# atmega128rf.net
KiCad netlist of a schematic drawn in Altium Designer
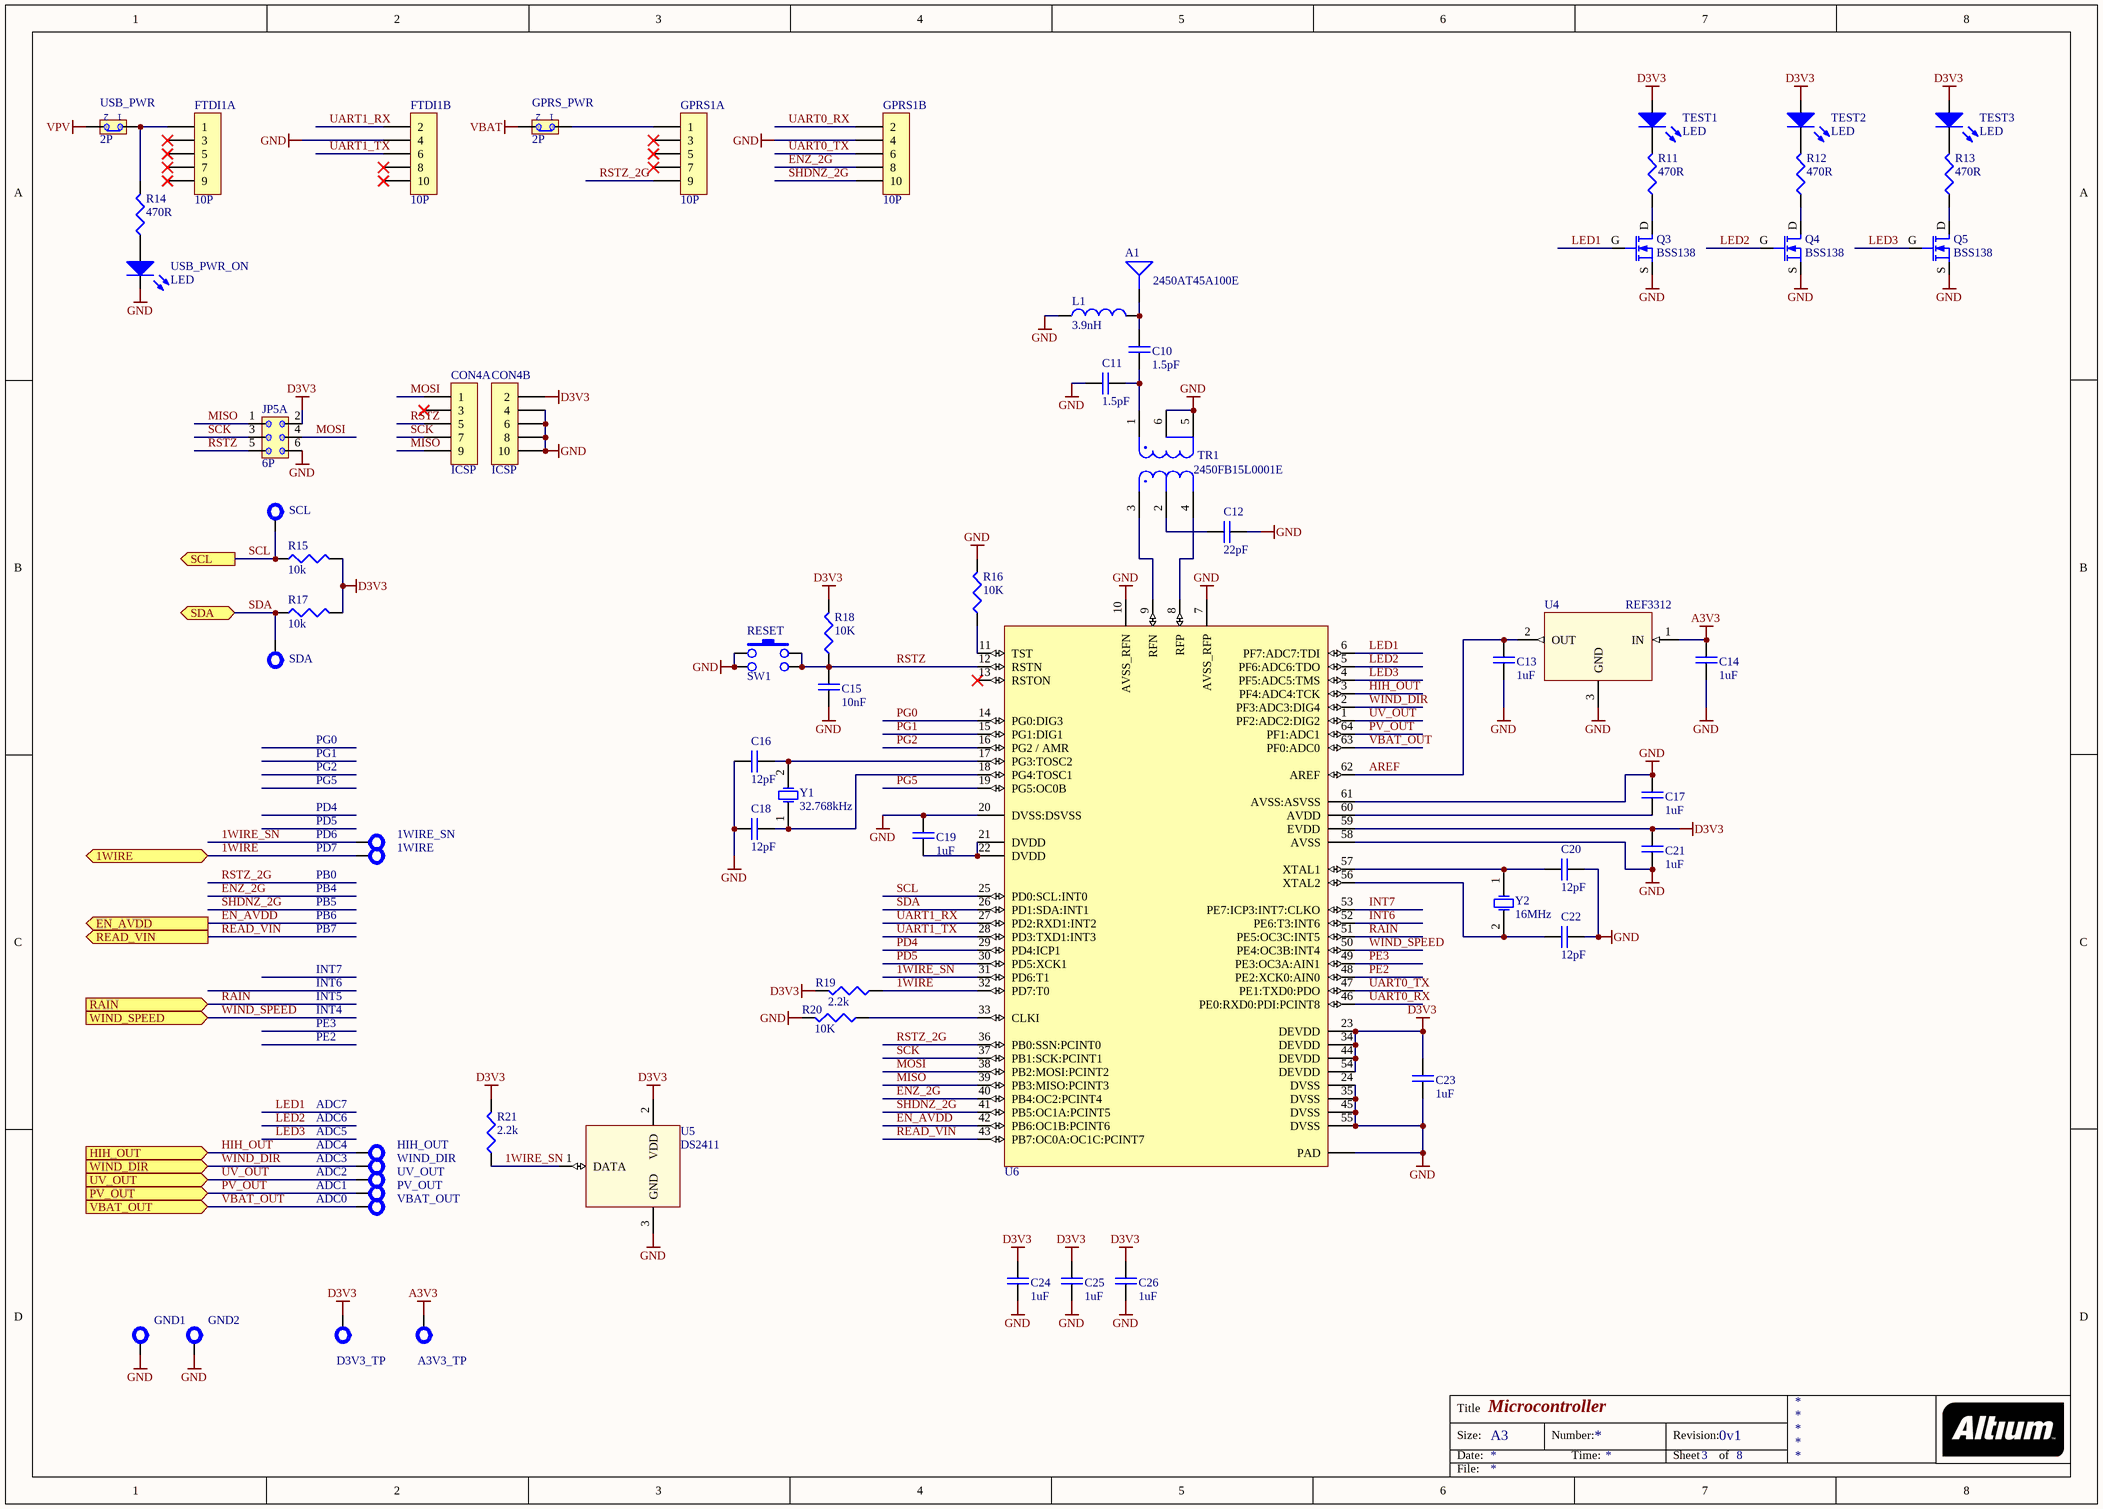
[diagram p0: atmega128rf.SchDoc]

(export (version "E")
  (design (tool "Eeschema 10.0.6"))
  (components
    (comp (ref "1WIRE")
      (value "Test Point")
      (footprint "TERMINAL")
      (description "Test/Probe Point")
      (fields (field (name "OWNER") "Nuno Brum"))
      (libsource (lib "Alcetronics_EM") (part "TEST-PROBE"))
    )
    (comp (ref "1WIRE_SN")
      (value "Test Point")
      (footprint "TERMINAL")
      (description "Test/Probe Point")
      (fields (field (name "OWNER") "Nuno Brum"))
      (libsource (lib "Alcetronics_EM") (part "TEST-PROBE"))
    )
    (comp (ref "A1")
      (value "2450AT45A100E")
      (footprint "2450AT45A100E")
      (description "ANTENNA")
      (libsource (lib "Alcetronics_Devices") (part "Antenna SE"))
    )
    (comp (ref "A3V3_TP")
      (value "Test Point")
      (footprint "TERMINAL")
      (description "Test/Probe Point")
      (fields (field (name "OWNER") "Nuno Brum"))
      (libsource (lib "Alcetronics_EM") (part "TEST-PROBE"))
    )
    (comp (ref "C10")
      (value "1.5pF")
      (footprint "0402")
      (description "Capacitor")
      (fields (field (name "OWNER") "Nuno Brum"))
      (libsource (lib "Alcetronics_Devices") (part "CAP"))
    )
    (comp (ref "C11")
      (value "1.5pF")
      (footprint "0402")
      (description "Capacitor")
      (fields (field (name "OWNER") "Nuno Brum"))
      (libsource (lib "Alcetronics_Devices") (part "CAP"))
    )
    (comp (ref "C12")
      (value "22pF")
      (footprint "0402")
      (description "Capacitor")
      (fields (field (name "OWNER") "Nuno Brum"))
      (libsource (lib "Alcetronics_Devices") (part "CAP"))
    )
    (comp (ref "C13")
      (value "1uF")
      (footprint "0603")
      (description "Capacitor")
      (fields (field (name "OWNER") "Nuno Brum"))
      (libsource (lib "Alcetronics_Devices") (part "CAP"))
    )
    (comp (ref "C14")
      (value "1uF")
      (footprint "0603")
      (description "Capacitor")
      (fields (field (name "OWNER") "Nuno Brum"))
      (libsource (lib "Alcetronics_Devices") (part "CAP"))
    )
    (comp (ref "C15")
      (value "10nF")
      (footprint "0603")
      (description "Capacitor")
      (fields (field (name "OWNER") "Nuno Brum"))
      (libsource (lib "Alcetronics_Devices") (part "CAP"))
    )
    (comp (ref "C16")
      (value "12pF")
      (footprint "0603")
      (description "Capacitor")
      (fields (field (name "OWNER") "Nuno Brum"))
      (libsource (lib "Alcetronics_Devices") (part "CAP"))
    )
    (comp (ref "C17")
      (value "1uF")
      (footprint "0603")
      (description "Capacitor")
      (fields (field (name "OWNER") "Nuno Brum"))
      (libsource (lib "Alcetronics_Devices") (part "CAP"))
    )
    (comp (ref "C18")
      (value "12pF")
      (footprint "0603")
      (description "Capacitor")
      (fields (field (name "OWNER") "Nuno Brum"))
      (libsource (lib "Alcetronics_Devices") (part "CAP"))
    )
    (comp (ref "C19")
      (value "1uF")
      (footprint "0603")
      (description "Capacitor")
      (fields (field (name "OWNER") "Nuno Brum"))
      (libsource (lib "Alcetronics_Devices") (part "CAP"))
    )
    (comp (ref "C20")
      (value "12pF")
      (footprint "0603")
      (description "Capacitor")
      (fields (field (name "OWNER") "Nuno Brum"))
      (libsource (lib "Alcetronics_Devices") (part "CAP"))
    )
    (comp (ref "C21")
      (value "1uF")
      (footprint "0603")
      (description "Capacitor")
      (fields (field (name "OWNER") "Nuno Brum"))
      (libsource (lib "Alcetronics_Devices") (part "CAP"))
    )
    (comp (ref "C22")
      (value "12pF")
      (footprint "0603")
      (description "Capacitor")
      (fields (field (name "OWNER") "Nuno Brum"))
      (libsource (lib "Alcetronics_Devices") (part "CAP"))
    )
    (comp (ref "C23")
      (value "1uF")
      (footprint "0603")
      (description "Capacitor")
      (fields (field (name "OWNER") "Nuno Brum"))
      (libsource (lib "Alcetronics_Devices") (part "CAP"))
    )
    (comp (ref "C24")
      (value "1uF")
      (footprint "0603")
      (description "Capacitor")
      (fields (field (name "OWNER") "Nuno Brum"))
      (libsource (lib "Alcetronics_Devices") (part "CAP"))
    )
    (comp (ref "C25")
      (value "1uF")
      (footprint "0603")
      (description "Capacitor")
      (fields (field (name "OWNER") "Nuno Brum"))
      (libsource (lib "Alcetronics_Devices") (part "CAP"))
    )
    (comp (ref "C26")
      (value "1uF")
      (footprint "0603")
      (description "Capacitor")
      (fields (field (name "OWNER") "Nuno Brum"))
      (libsource (lib "Alcetronics_Devices") (part "CAP"))
    )
    (comp (ref "CON4")
      (value "ICSP")
      (footprint "IDC-10-F")
      (description "Connector 10 Pins")
      (fields (field (name "OWNER") "António Silva"))
      (libsource (lib "Alcetronics_EM") (part "CON10"))
    )
    (comp (ref "D3V3_TP")
      (value "Test Point")
      (footprint "TERMINAL")
      (description "Test/Probe Point")
      (fields (field (name "OWNER") "Nuno Brum"))
      (libsource (lib "Alcetronics_EM") (part "TEST-PROBE"))
    )
    (comp (ref "FTDI1")
      (value "10P")
      (footprint "IDC-10-90")
      (description "Connector 10 Pins")
      (fields (field (name "OWNER") "António Silva"))
      (libsource (lib "Alcetronics_EM") (part "CON10"))
    )
    (comp (ref "GND1")
      (value "Test Point")
      (footprint "TEST-PROBE2")
      (description "Test/Probe Point")
      (fields (field (name "OWNER") "Nuno Brum"))
      (libsource (lib "Alcetronics_EM") (part "TEST-PROBE"))
    )
    (comp (ref "GND2")
      (value "Test Point")
      (footprint "TEST-PROBE2")
      (description "Test/Probe Point")
      (fields (field (name "OWNER") "Nuno Brum"))
      (libsource (lib "Alcetronics_EM") (part "TEST-PROBE"))
    )
    (comp (ref "GPRS1")
      (value "10P")
      (footprint "IDC-10-90")
      (description "Connector 10 Pins")
      (fields (field (name "OWNER") "António Silva"))
      (libsource (lib "Alcetronics_EM") (part "CON10"))
    )
    (comp (ref "GPRS_PWR")
      (value "2P")
      (footprint "SIP-2")
      (description "2-pin Jumper")
      (fields (field (name "OWNER") "Nuno Brum"))
      (libsource (lib "Alcetronics_EM") (part "JMP2"))
    )
    (comp (ref "HIH_OUT")
      (value "Test Point")
      (footprint "TERMINAL")
      (description "Test/Probe Point")
      (fields (field (name "OWNER") "Nuno Brum"))
      (libsource (lib "Alcetronics_EM") (part "TEST-PROBE"))
    )
    (comp (ref "JP5")
      (value "6P")
      (footprint "DIL-6")
      (description "6-Pin Jumper")
      (fields (field (name "OWNER") "Rui Rebelo"))
      (libsource (lib "Alcetronics_EM") (part "JMP6"))
    )
    (comp (ref "L1")
      (value "3.9nH")
      (footprint "0402")
      (description "Inductor")
      (fields (field (name "OWNER") "Nuno Brum"))
      (libsource (lib "Alcetronics_Devices") (part "IND"))
    )
    (comp (ref "PV_OUT")
      (value "Test Point")
      (footprint "TERMINAL")
      (description "Test/Probe Point")
      (fields (field (name "OWNER") "Nuno Brum"))
      (libsource (lib "Alcetronics_EM") (part "TEST-PROBE"))
    )
    (comp (ref "Q3")
      (value "BSS138")
      (footprint "SOT-23@GSD")
      (description "N-Channel Logic Level Enhancement Mode Field Effect Transistor")
      (fields (field (name "OWNER") "Nuno Brum"))
      (libsource (lib "Alcetronics_Devices") (part "MOSFET-N"))
    )
    (comp (ref "Q4")
      (value "BSS138")
      (footprint "SOT-23@GSD")
      (description "N-Channel Logic Level Enhancement Mode Field Effect Transistor")
      (fields (field (name "OWNER") "Nuno Brum"))
      (libsource (lib "Alcetronics_Devices") (part "MOSFET-N"))
    )
    (comp (ref "Q5")
      (value "BSS138")
      (footprint "SOT-23@GSD")
      (description "N-Channel Logic Level Enhancement Mode Field Effect Transistor")
      (fields (field (name "OWNER") "Nuno Brum"))
      (libsource (lib "Alcetronics_Devices") (part "MOSFET-N"))
    )
    (comp (ref "R11")
      (value "470R")
      (footprint "0603")
      (description "Resistor")
      (fields (field (name "OWNER") "Nuno Brum"))
      (libsource (lib "Alcetronics_Devices") (part "RES"))
    )
    (comp (ref "R12")
      (value "470R")
      (footprint "0603")
      (description "Resistor")
      (fields (field (name "OWNER") "Nuno Brum"))
      (libsource (lib "Alcetronics_Devices") (part "RES"))
    )
    (comp (ref "R13")
      (value "470R")
      (footprint "0603")
      (description "Resistor")
      (fields (field (name "OWNER") "Nuno Brum"))
      (libsource (lib "Alcetronics_Devices") (part "RES"))
    )
    (comp (ref "R14")
      (value "470R")
      (footprint "0603")
      (description "Resistor")
      (fields (field (name "OWNER") "Nuno Brum"))
      (libsource (lib "Alcetronics_Devices") (part "RES"))
    )
    (comp (ref "R15")
      (value "10k")
      (footprint "0603")
      (description "Resistor")
      (fields (field (name "OWNER") "Nuno Brum"))
      (libsource (lib "Alcetronics_Devices") (part "RES"))
    )
    (comp (ref "R16")
      (value "10K")
      (footprint "0603")
      (description "Resistor")
      (fields (field (name "OWNER") "Nuno Brum"))
      (libsource (lib "Alcetronics_Devices") (part "RES"))
    )
    (comp (ref "R17")
      (value "10k")
      (footprint "0603")
      (description "Resistor")
      (fields (field (name "OWNER") "Nuno Brum"))
      (libsource (lib "Alcetronics_Devices") (part "RES"))
    )
    (comp (ref "R18")
      (value "10K")
      (footprint "0603")
      (description "Resistor")
      (fields (field (name "OWNER") "Nuno Brum"))
      (libsource (lib "Alcetronics_Devices") (part "RES"))
    )
    (comp (ref "R19")
      (value "2.2k")
      (footprint "0603")
      (description "Resistor")
      (fields (field (name "OWNER") "Nuno Brum"))
      (libsource (lib "Alcetronics_Devices") (part "RES"))
    )
    (comp (ref "R20")
      (value "10K")
      (footprint "0603")
      (description "Resistor")
      (fields (field (name "OWNER") "Nuno Brum"))
      (libsource (lib "Alcetronics_Devices") (part "RES"))
    )
    (comp (ref "R21")
      (value "2.2k")
      (footprint "0603")
      (description "Resistor")
      (fields (field (name "OWNER") "Nuno Brum"))
      (libsource (lib "Alcetronics_Devices") (part "RES"))
    )
    (comp (ref "RESET")
      (value "SW1")
      (footprint "MICROSWITCH")
      (description "Switch Push Button")
      (fields (field (name "OWNER") "Nuno Brum"))
      (libsource (lib "Alcetronics_EM") (part "SW1"))
    )
    (comp (ref "SCL")
      (value "Test Point")
      (footprint "TERMINAL")
      (description "Test/Probe Point")
      (fields (field (name "OWNER") "Nuno Brum"))
      (libsource (lib "Alcetronics_EM") (part "TEST-PROBE"))
    )
    (comp (ref "SDA")
      (value "Test Point")
      (footprint "TERMINAL")
      (description "Test/Probe Point")
      (fields (field (name "OWNER") "Nuno Brum"))
      (libsource (lib "Alcetronics_EM") (part "TEST-PROBE"))
    )
    (comp (ref "TEST1")
      (value "LED")
      (footprint "0805@DIODE")
      (description "Light emitting diode")
      (fields (field (name "OWNER") "Nuno Brum"))
      (libsource (lib "Alcetronics_Devices") (part "LED"))
    )
    (comp (ref "TEST2")
      (value "LED")
      (footprint "0805@DIODE")
      (description "Light emitting diode")
      (fields (field (name "OWNER") "Nuno Brum"))
      (libsource (lib "Alcetronics_Devices") (part "LED"))
    )
    (comp (ref "TEST3")
      (value "LED")
      (footprint "0805@DIODE")
      (description "Light emitting diode")
      (fields (field (name "OWNER") "Nuno Brum"))
      (libsource (lib "Alcetronics_Devices") (part "LED"))
    )
    (comp (ref "TR1")
      (value "2450FB15L0001E")
      (footprint "0805@BALUN")
      (description "FILTER BALUN ATMEL 2.45GHZ")
      (fields (field (name "OWNER") "Rui Rebelo"))
      (libsource (lib "Alcetronics_Devices") (part "2450FB15L0001E"))
    )
    (comp (ref "U4")
      (value "REF3312")
      (footprint "SOT-23")
      (description "Voltage Reference 1.25V, 30ppm/degC, 5mA")
      (libsource (lib "Alcetronics_IC") (part "REF3312"))
    )
    (comp (ref "U5")
      (value "DS2411")
      (footprint "SOT-23")
      (description "Silicon Serial Number")
      (libsource (lib "Alcetronics_IC") (part "DS2411"))
    )
    (comp (ref "U6")
      (value "ATmega128RFA1")
      (footprint "QFN-64@EP")
      (description "802.15.4 compliant AVR transceiver")
      (fields (field (name "VERIFIED BY") "vlarsen"))
      (libsource (lib "Alcetronics_IC") (part "ATmega128RFA1"))
    )
    (comp (ref "USB_PWR")
      (value "2P")
      (footprint "SIP-2")
      (description "2-pin Jumper")
      (fields (field (name "OWNER") "Nuno Brum"))
      (libsource (lib "Alcetronics_EM") (part "JMP2"))
    )
    (comp (ref "USB_PWR_ON")
      (value "LED")
      (footprint "0805@DIODE")
      (description "Light emitting diode")
      (fields (field (name "OWNER") "Nuno Brum"))
      (libsource (lib "Alcetronics_Devices") (part "LED"))
    )
    (comp (ref "UV_OUT")
      (value "Test Point")
      (footprint "TERMINAL")
      (description "Test/Probe Point")
      (fields (field (name "OWNER") "Nuno Brum"))
      (libsource (lib "Alcetronics_EM") (part "TEST-PROBE"))
    )
    (comp (ref "VBAT_OUT")
      (value "Test Point")
      (footprint "TERMINAL")
      (description "Test/Probe Point")
      (fields (field (name "OWNER") "Nuno Brum"))
      (libsource (lib "Alcetronics_EM") (part "TEST-PROBE"))
    )
    (comp (ref "WIND_DIR")
      (value "Test Point")
      (footprint "TERMINAL")
      (description "Test/Probe Point")
      (fields (field (name "OWNER") "Nuno Brum"))
      (libsource (lib "Alcetronics_EM") (part "TEST-PROBE"))
    )
    (comp (ref "Y1")
      (value "32.768kHz")
      (footprint "HC-49U")
      (description "Crystal Oscillator")
      (fields (field (name "PUBLISHER") "Altium Limited"))
      (libsource (lib "Alcetronics_Devices") (part "Crystal Oscillator"))
    )
    (comp (ref "Y2")
      (value "16MHz")
      (footprint "HC-49U")
      (description "Crystal Oscillator")
      (fields (field (name "PUBLISHER") "Altium Limited"))
      (libsource (lib "Alcetronics_Devices") (part "Crystal Oscillator"))
    )
  )
  (nets
    (net (code "1") (name "/1WIRE") (class "Default")
      (node (ref "1WIRE") (pin "1") (pinfunction "TP_1") (pintype "passive"))
      (node (ref "R19") (pin "1") (pinfunction "1_1") (pintype "passive"))
      (node (ref "U6") (pin "32") (pinfunction "PD7:T0_32") (pintype "bidirectional"))
    )
    (net (code "2") (name "/1WIRE_SN") (class "Default")
      (node (ref "1WIRE_SN") (pin "1") (pinfunction "TP_1") (pintype "passive"))
      (node (ref "R21") (pin "1") (pinfunction "1_1") (pintype "passive"))
      (node (ref "U5") (pin "1") (pinfunction "DATA_1") (pintype "bidirectional"))
      (node (ref "U6") (pin "31") (pinfunction "PD6:T1_31") (pintype "bidirectional"))
    )
    (net (code "3") (name "/AREF") (class "Default")
      (node (ref "C13") (pin "1") (pinfunction "1_1") (pintype "passive"))
      (node (ref "U4") (pin "2") (pinfunction "OUT_2") (pintype "output"))
      (node (ref "U6") (pin "62") (pinfunction "AREF_62") (pintype "bidirectional"))
    )
    (net (code "4") (name "/ENZ_2G") (class "Default")
      (node (ref "GPRS1") (pin "8") (pinfunction "8_8") (pintype "passive"))
      (node (ref "U6") (pin "40") (pinfunction "PB4:OC2:PCINT4_40") (pintype "bidirectional"))
    )
    (net (code "5") (name "/EN_AVDD") (class "Default")
      (node (ref "U6") (pin "42") (pinfunction "PB6:OC1B:PCINT6_42") (pintype "bidirectional"))
    )
    (net (code "6") (name "/HIH_OUT") (class "Default")
      (node (ref "HIH_OUT") (pin "1") (pinfunction "TP_1") (pintype "passive"))
      (node (ref "U6") (pin "3") (pinfunction "PF4:ADC4:TCK_3") (pintype "bidirectional"))
    )
    (net (code "7") (name "/INT6") (class "Default")
      (node (ref "U6") (pin "52") (pinfunction "PE6:T3:INT6_52") (pintype "bidirectional"))
    )
    (net (code "8") (name "/INT7") (class "Default")
      (node (ref "U6") (pin "53") (pinfunction "PE7:ICP3:INT7:CLKO_53") (pintype "bidirectional"))
    )
    (net (code "9") (name "/LED1") (class "Default")
      (node (ref "Q3") (pin "G") (pinfunction "G_G") (pintype "passive"))
      (node (ref "U6") (pin "6") (pinfunction "PF7:ADC7:TDI_6") (pintype "bidirectional"))
    )
    (net (code "10") (name "/LED2") (class "Default")
      (node (ref "Q4") (pin "G") (pinfunction "G_G") (pintype "passive"))
      (node (ref "U6") (pin "5") (pinfunction "PF6:ADC6:TDO_5") (pintype "bidirectional"))
    )
    (net (code "11") (name "/LED3") (class "Default")
      (node (ref "Q5") (pin "G") (pinfunction "G_G") (pintype "passive"))
      (node (ref "U6") (pin "4") (pinfunction "PF5:ADC5:TMS_4") (pintype "bidirectional"))
    )
    (net (code "12") (name "/MISO") (class "Default")
      (node (ref "CON4") (pin "9") (pinfunction "9_9") (pintype "passive"))
      (node (ref "JP5") (pin "1") (pinfunction "1_1") (pintype "passive"))
      (node (ref "U6") (pin "39") (pinfunction "PB3:MISO:PCINT3_39") (pintype "bidirectional"))
    )
    (net (code "13") (name "/MOSI") (class "Default")
      (node (ref "CON4") (pin "1") (pinfunction "1_1") (pintype "passive"))
      (node (ref "JP5") (pin "4") (pinfunction "4_4") (pintype "passive"))
      (node (ref "U6") (pin "38") (pinfunction "PB2:MOSI:PCINT2_38") (pintype "bidirectional"))
    )
    (net (code "14") (name "/PD4") (class "Default")
      (node (ref "U6") (pin "29") (pinfunction "PD4:ICP1_29") (pintype "bidirectional"))
    )
    (net (code "15") (name "/PD5") (class "Default")
      (node (ref "U6") (pin "30") (pinfunction "PD5:XCK1_30") (pintype "bidirectional"))
    )
    (net (code "16") (name "/PE2") (class "Default")
      (node (ref "U6") (pin "48") (pinfunction "PE2:XCK0:AIN0_48") (pintype "bidirectional"))
    )
    (net (code "17") (name "/PE3") (class "Default")
      (node (ref "U6") (pin "49") (pinfunction "PE3:OC3A:AIN1_49") (pintype "bidirectional"))
    )
    (net (code "18") (name "/PG0") (class "Default")
      (node (ref "U6") (pin "14") (pinfunction "PG0:DIG3_14") (pintype "bidirectional"))
    )
    (net (code "19") (name "/PG1") (class "Default")
      (node (ref "U6") (pin "15") (pinfunction "PG1:DIG1_15") (pintype "bidirectional"))
    )
    (net (code "20") (name "/PG2") (class "Default")
      (node (ref "U6") (pin "16") (pinfunction "PG2_/_AMR_16") (pintype "bidirectional"))
    )
    (net (code "21") (name "/PG5") (class "Default")
      (node (ref "U6") (pin "19") (pinfunction "PG5:OC0B_19") (pintype "bidirectional"))
    )
    (net (code "22") (name "/PV_OUT") (class "Default")
      (node (ref "PV_OUT") (pin "1") (pinfunction "TP_1") (pintype "passive"))
      (node (ref "U6") (pin "64") (pinfunction "PF1:ADC1_64") (pintype "bidirectional"))
    )
    (net (code "23") (name "/RAIN") (class "Default")
      (node (ref "U6") (pin "51") (pinfunction "PE5:OC3C:INT5_51") (pintype "bidirectional"))
    )
    (net (code "24") (name "/READ_VIN") (class "Default")
      (node (ref "U6") (pin "43") (pinfunction "PB7:OC0A:OC1C:PCINT7_43") (pintype "bidirectional"))
    )
    (net (code "25") (name "/RSTZ") (class "Default")
      (node (ref "C15") (pin "1") (pinfunction "1_1") (pintype "passive"))
      (node (ref "CON4") (pin "5") (pinfunction "5_5") (pintype "passive"))
      (node (ref "JP5") (pin "5") (pinfunction "5_5") (pintype "passive"))
      (node (ref "R18") (pin "1") (pinfunction "1_1") (pintype "passive"))
      (node (ref "RESET") (pin "2") (pinfunction "2_2") (pintype "passive"))
      (node (ref "RESET") (pin "4") (pinfunction "4_4") (pintype "passive"))
      (node (ref "U6") (pin "12") (pinfunction "RSTN_12") (pintype "bidirectional"))
    )
    (net (code "26") (name "/RSTZ_2G") (class "Default")
      (node (ref "GPRS1") (pin "9") (pinfunction "9_9") (pintype "passive"))
      (node (ref "U6") (pin "36") (pinfunction "PB0:SSN:PCINT0_36") (pintype "bidirectional"))
    )
    (net (code "27") (name "/SCK") (class "Default")
      (node (ref "CON4") (pin "7") (pinfunction "7_7") (pintype "passive"))
      (node (ref "JP5") (pin "3") (pinfunction "3_3") (pintype "passive"))
      (node (ref "U6") (pin "37") (pinfunction "PB1:SCK:PCINT1_37") (pintype "bidirectional"))
    )
    (net (code "28") (name "/SCL") (class "Default")
      (node (ref "R15") (pin "1") (pinfunction "1_1") (pintype "passive"))
      (node (ref "SCL") (pin "1") (pinfunction "TP_1") (pintype "passive"))
      (node (ref "U6") (pin "25") (pinfunction "PD0:SCL:INT0_25") (pintype "bidirectional"))
    )
    (net (code "29") (name "/SDA") (class "Default")
      (node (ref "R17") (pin "1") (pinfunction "1_1") (pintype "passive"))
      (node (ref "SDA") (pin "1") (pinfunction "TP_1") (pintype "passive"))
      (node (ref "U6") (pin "26") (pinfunction "PD1:SDA:INT1_26") (pintype "bidirectional"))
    )
    (net (code "30") (name "/SHDNZ_2G") (class "Default")
      (node (ref "GPRS1") (pin "10") (pinfunction "10_10") (pintype "passive"))
      (node (ref "U6") (pin "41") (pinfunction "PB5:OC1A:PCINT5_41") (pintype "bidirectional"))
    )
    (net (code "31") (name "/UART0_RX") (class "Default")
      (node (ref "GPRS1") (pin "2") (pinfunction "2_2") (pintype "passive"))
      (node (ref "U6") (pin "46") (pinfunction "PE0:RXD0:PDI:PCINT8_46") (pintype "bidirectional"))
    )
    (net (code "32") (name "/UART0_TX") (class "Default")
      (node (ref "GPRS1") (pin "6") (pinfunction "6_6") (pintype "passive"))
      (node (ref "U6") (pin "47") (pinfunction "PE1:TXD0:PDO_47") (pintype "bidirectional"))
    )
    (net (code "33") (name "/UART1_RX") (class "Default")
      (node (ref "FTDI1") (pin "2") (pinfunction "2_2") (pintype "passive"))
      (node (ref "U6") (pin "27") (pinfunction "PD2:RXD1:INT2_27") (pintype "bidirectional"))
    )
    (net (code "34") (name "/UART1_TX") (class "Default")
      (node (ref "FTDI1") (pin "6") (pinfunction "6_6") (pintype "passive"))
      (node (ref "U6") (pin "28") (pinfunction "PD3:TXD1:INT3_28") (pintype "bidirectional"))
    )
    (net (code "35") (name "/UV_OUT") (class "Default")
      (node (ref "U6") (pin "1") (pinfunction "PF2:ADC2:DIG2_1") (pintype "bidirectional"))
      (node (ref "UV_OUT") (pin "1") (pinfunction "TP_1") (pintype "passive"))
    )
    (net (code "36") (name "/VBAT_OUT") (class "Default")
      (node (ref "U6") (pin "63") (pinfunction "PF0:ADC0_63") (pintype "bidirectional"))
      (node (ref "VBAT_OUT") (pin "1") (pinfunction "TP_1") (pintype "passive"))
    )
    (net (code "37") (name "/WIND_DIR") (class "Default")
      (node (ref "U6") (pin "2") (pinfunction "PF3:ADC3:DIG4_2") (pintype "bidirectional"))
      (node (ref "WIND_DIR") (pin "1") (pinfunction "TP_1") (pintype "passive"))
    )
    (net (code "38") (name "/WIND_SPEED") (class "Default")
      (node (ref "U6") (pin "50") (pinfunction "PE4:OC3B:INT4_50") (pintype "bidirectional"))
    )
    (net (code "39") (name "A3V3") (class "Default")
      (node (ref "A3V3_TP") (pin "1") (pinfunction "TP_1") (pintype "passive"))
      (node (ref "C14") (pin "1") (pinfunction "1_1") (pintype "passive"))
      (node (ref "U4") (pin "1") (pinfunction "IN_1") (pintype "input"))
    )
    (net (code "40") (name "D3V3") (class "Default")
      (node (ref "C21") (pin "2") (pinfunction "2_2") (pintype "passive"))
      (node (ref "C23") (pin "2") (pinfunction "2_2") (pintype "passive"))
      (node (ref "C24") (pin "2") (pinfunction "2_2") (pintype "passive"))
      (node (ref "C25") (pin "2") (pinfunction "2_2") (pintype "passive"))
      (node (ref "C26") (pin "2") (pinfunction "2_2") (pintype "passive"))
      (node (ref "CON4") (pin "2") (pinfunction "2_2") (pintype "passive"))
      (node (ref "D3V3_TP") (pin "1") (pinfunction "TP_1") (pintype "passive"))
      (node (ref "JP5") (pin "2") (pinfunction "2_2") (pintype "passive"))
      (node (ref "R15") (pin "2") (pinfunction "2_2") (pintype "passive"))
      (node (ref "R17") (pin "2") (pinfunction "2_2") (pintype "passive"))
      (node (ref "R18") (pin "2") (pinfunction "2_2") (pintype "passive"))
      (node (ref "R19") (pin "2") (pinfunction "2_2") (pintype "passive"))
      (node (ref "R21") (pin "2") (pinfunction "2_2") (pintype "passive"))
      (node (ref "TEST1") (pin "A") (pinfunction "A_A") (pintype "passive"))
      (node (ref "TEST2") (pin "A") (pinfunction "A_A") (pintype "passive"))
      (node (ref "TEST3") (pin "A") (pinfunction "A_A") (pintype "passive"))
      (node (ref "U5") (pin "2") (pinfunction "VDD_2") (pintype "power_in"))
      (node (ref "U6") (pin "23") (pinfunction "DEVDD_23") (pintype "power_in"))
      (node (ref "U6") (pin "34") (pinfunction "DEVDD_34") (pintype "power_in"))
      (node (ref "U6") (pin "44") (pinfunction "DEVDD_44") (pintype "power_in"))
      (node (ref "U6") (pin "54") (pinfunction "DEVDD_54") (pintype "power_in"))
      (node (ref "U6") (pin "59") (pinfunction "EVDD_59") (pintype "power_in"))
    )
    (net (code "41") (name "GND") (class "Default")
      (node (ref "C11") (pin "1") (pinfunction "1_1") (pintype "passive"))
      (node (ref "C12") (pin "2") (pinfunction "2_2") (pintype "passive"))
      (node (ref "C13") (pin "2") (pinfunction "2_2") (pintype "passive"))
      (node (ref "C14") (pin "2") (pinfunction "2_2") (pintype "passive"))
      (node (ref "C15") (pin "2") (pinfunction "2_2") (pintype "passive"))
      (node (ref "C16") (pin "1") (pinfunction "1_1") (pintype "passive"))
      (node (ref "C17") (pin "2") (pinfunction "2_2") (pintype "passive"))
      (node (ref "C18") (pin "1") (pinfunction "1_1") (pintype "passive"))
      (node (ref "C19") (pin "2") (pinfunction "2_2") (pintype "passive"))
      (node (ref "C20") (pin "2") (pinfunction "2_2") (pintype "passive"))
      (node (ref "C21") (pin "1") (pinfunction "1_1") (pintype "passive"))
      (node (ref "C22") (pin "2") (pinfunction "2_2") (pintype "passive"))
      (node (ref "C23") (pin "1") (pinfunction "1_1") (pintype "passive"))
      (node (ref "C24") (pin "1") (pinfunction "1_1") (pintype "passive"))
      (node (ref "C25") (pin "1") (pinfunction "1_1") (pintype "passive"))
      (node (ref "C26") (pin "1") (pinfunction "1_1") (pintype "passive"))
      (node (ref "CON4") (pin "10") (pinfunction "10_10") (pintype "passive"))
      (node (ref "CON4") (pin "4") (pinfunction "4_4") (pintype "passive"))
      (node (ref "CON4") (pin "6") (pinfunction "6_6") (pintype "passive"))
      (node (ref "CON4") (pin "8") (pinfunction "8_8") (pintype "passive"))
      (node (ref "FTDI1") (pin "4") (pinfunction "4_4") (pintype "passive"))
      (node (ref "GND1") (pin "1") (pinfunction "TP_1") (pintype "passive"))
      (node (ref "GND2") (pin "1") (pinfunction "TP_1") (pintype "passive"))
      (node (ref "GPRS1") (pin "4") (pinfunction "4_4") (pintype "passive"))
      (node (ref "JP5") (pin "6") (pinfunction "6_6") (pintype "passive"))
      (node (ref "L1") (pin "1") (pinfunction "1_1") (pintype "passive"))
      (node (ref "Q3") (pin "S") (pinfunction "S_S") (pintype "passive"))
      (node (ref "Q4") (pin "S") (pinfunction "S_S") (pintype "passive"))
      (node (ref "Q5") (pin "S") (pinfunction "S_S") (pintype "passive"))
      (node (ref "R16") (pin "2") (pinfunction "2_2") (pintype "passive"))
      (node (ref "R20") (pin "2") (pinfunction "2_2") (pintype "passive"))
      (node (ref "RESET") (pin "1") (pinfunction "1_1") (pintype "passive"))
      (node (ref "RESET") (pin "3") (pinfunction "3_3") (pintype "passive"))
      (node (ref "TR1") (pin "5") (pinfunction "Ground_5") (pintype "passive"))
      (node (ref "TR1") (pin "6") (pinfunction "Ground_6") (pintype "passive"))
      (node (ref "U4") (pin "3") (pinfunction "GND_3") (pintype "power_in"))
      (node (ref "U5") (pin "3") (pinfunction "GND_3") (pintype "power_in"))
      (node (ref "U6") (pin "10") (pinfunction "AVSS_RFN_10") (pintype "power_in"))
      (node (ref "U6") (pin "20") (pinfunction "DVSS:DSVSS_20") (pintype "power_in"))
      (node (ref "U6") (pin "24") (pinfunction "DVSS_24") (pintype "power_in"))
      (node (ref "U6") (pin "35") (pinfunction "DVSS_35") (pintype "power_in"))
      (node (ref "U6") (pin "45") (pinfunction "DVSS_45") (pintype "power_in"))
      (node (ref "U6") (pin "55") (pinfunction "DVSS_55") (pintype "power_in"))
      (node (ref "U6") (pin "58") (pinfunction "AVSS_58") (pintype "power_in"))
      (node (ref "U6") (pin "61") (pinfunction "AVSS:ASVSS_61") (pintype "power_in"))
      (node (ref "U6") (pin "7") (pinfunction "AVSS_RFP_7") (pintype "power_in"))
      (node (ref "U6") (pin "PAD") (pinfunction "PAD_PAD") (pintype "power_in"))
      (node (ref "USB_PWR_ON") (pin "K") (pinfunction "K_K") (pintype "passive"))
    )
    (net (code "42") (name "Net-(A1-Pad1)") (class "Default")
      (node (ref "A1") (pin "1") (pinfunction "1_1") (pintype "passive"))
      (node (ref "C10") (pin "2") (pinfunction "2_2") (pintype "passive"))
      (node (ref "L1") (pin "2") (pinfunction "2_2") (pintype "passive"))
    )
    (net (code "43") (name "Net-(C19-Pad1)") (class "Default")
      (node (ref "C19") (pin "1") (pinfunction "1_1") (pintype "passive"))
      (node (ref "U6") (pin "21") (pinfunction "DVDD_21") (pintype "power_in"))
      (node (ref "U6") (pin "22") (pinfunction "DVDD_22") (pintype "power_in"))
    )
    (net (code "44") (name "Net-(FTDI1-Pad1)") (class "Default")
      (node (ref "FTDI1") (pin "1") (pinfunction "1_1") (pintype "passive"))
      (node (ref "R14") (pin "2") (pinfunction "2_2") (pintype "passive"))
      (node (ref "USB_PWR") (pin "1") (pinfunction "1_1") (pintype "passive"))
    )
    (net (code "45") (name "Net-(GPRS1-Pad1)") (class "Default")
      (node (ref "GPRS1") (pin "1") (pinfunction "1_1") (pintype "passive"))
      (node (ref "GPRS_PWR") (pin "1") (pinfunction "1_1") (pintype "passive"))
    )
    (net (code "46") (name "Net-(Q3-PadD)") (class "Default")
      (node (ref "Q3") (pin "D") (pinfunction "D_D") (pintype "passive"))
      (node (ref "R11") (pin "1") (pinfunction "1_1") (pintype "passive"))
    )
    (net (code "47") (name "Net-(Q4-PadD)") (class "Default")
      (node (ref "Q4") (pin "D") (pinfunction "D_D") (pintype "passive"))
      (node (ref "R12") (pin "1") (pinfunction "1_1") (pintype "passive"))
    )
    (net (code "48") (name "Net-(Q5-PadD)") (class "Default")
      (node (ref "Q5") (pin "D") (pinfunction "D_D") (pintype "passive"))
      (node (ref "R13") (pin "1") (pinfunction "1_1") (pintype "passive"))
    )
    (net (code "49") (name "Net-(R11-Pad2)") (class "Default")
      (node (ref "R11") (pin "2") (pinfunction "2_2") (pintype "passive"))
      (node (ref "TEST1") (pin "K") (pinfunction "K_K") (pintype "passive"))
    )
    (net (code "50") (name "Net-(R12-Pad2)") (class "Default")
      (node (ref "R12") (pin "2") (pinfunction "2_2") (pintype "passive"))
      (node (ref "TEST2") (pin "K") (pinfunction "K_K") (pintype "passive"))
    )
    (net (code "51") (name "Net-(R13-Pad2)") (class "Default")
      (node (ref "R13") (pin "2") (pinfunction "2_2") (pintype "passive"))
      (node (ref "TEST3") (pin "K") (pinfunction "K_K") (pintype "passive"))
    )
    (net (code "52") (name "Net-(R14-Pad1)") (class "Default")
      (node (ref "R14") (pin "1") (pinfunction "1_1") (pintype "passive"))
      (node (ref "USB_PWR_ON") (pin "A") (pinfunction "A_A") (pintype "passive"))
    )
    (net (code "53") (name "Net-(TR1-DC_Feed_+_RF_GND)") (class "Default")
      (node (ref "C12") (pin "1") (pinfunction "1_1") (pintype "passive"))
      (node (ref "TR1") (pin "2") (pinfunction "DC_Feed_+_RF_GND_2") (pintype "passive"))
    )
    (net (code "54") (name "Net-(TR1-Unbalanced_Port)") (class "Default")
      (node (ref "C10") (pin "1") (pinfunction "1_1") (pintype "passive"))
      (node (ref "C11") (pin "2") (pinfunction "2_2") (pintype "passive"))
      (node (ref "TR1") (pin "1") (pinfunction "Unbalanced_Port_1") (pintype "passive"))
    )
    (net (code "55") (name "Net-(U6-AVDD)") (class "Default")
      (node (ref "C17") (pin "1") (pinfunction "1_1") (pintype "passive"))
      (node (ref "U6") (pin "60") (pinfunction "AVDD_60") (pintype "power_in"))
    )
    (net (code "56") (name "Net-(U6-CLKI)") (class "Default")
      (node (ref "R20") (pin "1") (pinfunction "1_1") (pintype "passive"))
      (node (ref "U6") (pin "33") (pinfunction "CLKI_33") (pintype "bidirectional"))
    )
    (net (code "57") (name "Net-(U6-PG3:TOSC2)") (class "Default")
      (node (ref "C16") (pin "2") (pinfunction "2_2") (pintype "passive"))
      (node (ref "U6") (pin "17") (pinfunction "PG3:TOSC2_17") (pintype "bidirectional"))
      (node (ref "Y1") (pin "2") (pinfunction "OSC2_2") (pintype "passive"))
    )
    (net (code "58") (name "Net-(U6-PG4:TOSC1)") (class "Default")
      (node (ref "C18") (pin "2") (pinfunction "2_2") (pintype "passive"))
      (node (ref "U6") (pin "18") (pinfunction "PG4:TOSC1_18") (pintype "bidirectional"))
      (node (ref "Y1") (pin "1") (pinfunction "OSC1_1") (pintype "passive"))
    )
    (net (code "59") (name "Net-(U6-RFN)") (class "Default")
      (node (ref "TR1") (pin "3") (pinfunction "Balanced_Port_3") (pintype "passive"))
      (node (ref "U6") (pin "9") (pinfunction "RFN_9") (pintype "bidirectional"))
    )
    (net (code "60") (name "Net-(U6-RFP)") (class "Default")
      (node (ref "TR1") (pin "4") (pinfunction "Balanced_Port_4") (pintype "passive"))
      (node (ref "U6") (pin "8") (pinfunction "RFP_8") (pintype "bidirectional"))
    )
    (net (code "61") (name "Net-(U6-TST)") (class "Default")
      (node (ref "R16") (pin "1") (pinfunction "1_1") (pintype "passive"))
      (node (ref "U6") (pin "11") (pinfunction "TST_11") (pintype "bidirectional"))
    )
    (net (code "62") (name "Net-(U6-XTAL1)") (class "Default")
      (node (ref "C20") (pin "1") (pinfunction "1_1") (pintype "passive"))
      (node (ref "U6") (pin "57") (pinfunction "XTAL1_57") (pintype "bidirectional"))
      (node (ref "Y2") (pin "1") (pinfunction "OSC1_1") (pintype "passive"))
    )
    (net (code "63") (name "Net-(U6-XTAL2)") (class "Default")
      (node (ref "C22") (pin "1") (pinfunction "1_1") (pintype "passive"))
      (node (ref "U6") (pin "56") (pinfunction "XTAL2_56") (pintype "bidirectional"))
      (node (ref "Y2") (pin "2") (pinfunction "OSC2_2") (pintype "passive"))
    )
    (net (code "64") (name "VBAT") (class "Default")
      (node (ref "GPRS_PWR") (pin "2") (pinfunction "2_2") (pintype "passive"))
    )
    (net (code "65") (name "VPV") (class "Default")
      (node (ref "USB_PWR") (pin "2") (pinfunction "2_2") (pintype "passive"))
    )
    (net (code "66") (name "unconnected-(CON4-Pad3)") (class "Default")
      (node (ref "CON4") (pin "3") (pinfunction "3_3") (pintype "passive+no_connect"))
    )
    (net (code "67") (name "unconnected-(FTDI1-Pad3)") (class "Default")
      (node (ref "FTDI1") (pin "3") (pinfunction "3_3") (pintype "passive+no_connect"))
    )
    (net (code "68") (name "unconnected-(FTDI1-Pad5)") (class "Default")
      (node (ref "FTDI1") (pin "5") (pinfunction "5_5") (pintype "passive+no_connect"))
    )
    (net (code "69") (name "unconnected-(FTDI1-Pad7)") (class "Default")
      (node (ref "FTDI1") (pin "7") (pinfunction "7_7") (pintype "passive+no_connect"))
    )
    (net (code "70") (name "unconnected-(FTDI1-Pad8)") (class "Default")
      (node (ref "FTDI1") (pin "8") (pinfunction "8_8") (pintype "passive+no_connect"))
    )
    (net (code "71") (name "unconnected-(FTDI1-Pad9)") (class "Default")
      (node (ref "FTDI1") (pin "9") (pinfunction "9_9") (pintype "passive+no_connect"))
    )
    (net (code "72") (name "unconnected-(FTDI1-Pad10)") (class "Default")
      (node (ref "FTDI1") (pin "10") (pinfunction "10_10") (pintype "passive+no_connect"))
    )
    (net (code "73") (name "unconnected-(GPRS1-Pad3)") (class "Default")
      (node (ref "GPRS1") (pin "3") (pinfunction "3_3") (pintype "passive+no_connect"))
    )
    (net (code "74") (name "unconnected-(GPRS1-Pad5)") (class "Default")
      (node (ref "GPRS1") (pin "5") (pinfunction "5_5") (pintype "passive+no_connect"))
    )
    (net (code "75") (name "unconnected-(GPRS1-Pad7)") (class "Default")
      (node (ref "GPRS1") (pin "7") (pinfunction "7_7") (pintype "passive+no_connect"))
    )
    (net (code "76") (name "unconnected-(U6-RSTON-Pad13)") (class "Default")
      (node (ref "U6") (pin "13") (pinfunction "RSTON_13") (pintype "bidirectional+no_connect"))
    )
  )
)
